# Interfaces.net
KiCad netlist of a schematic drawn in Altium Designer
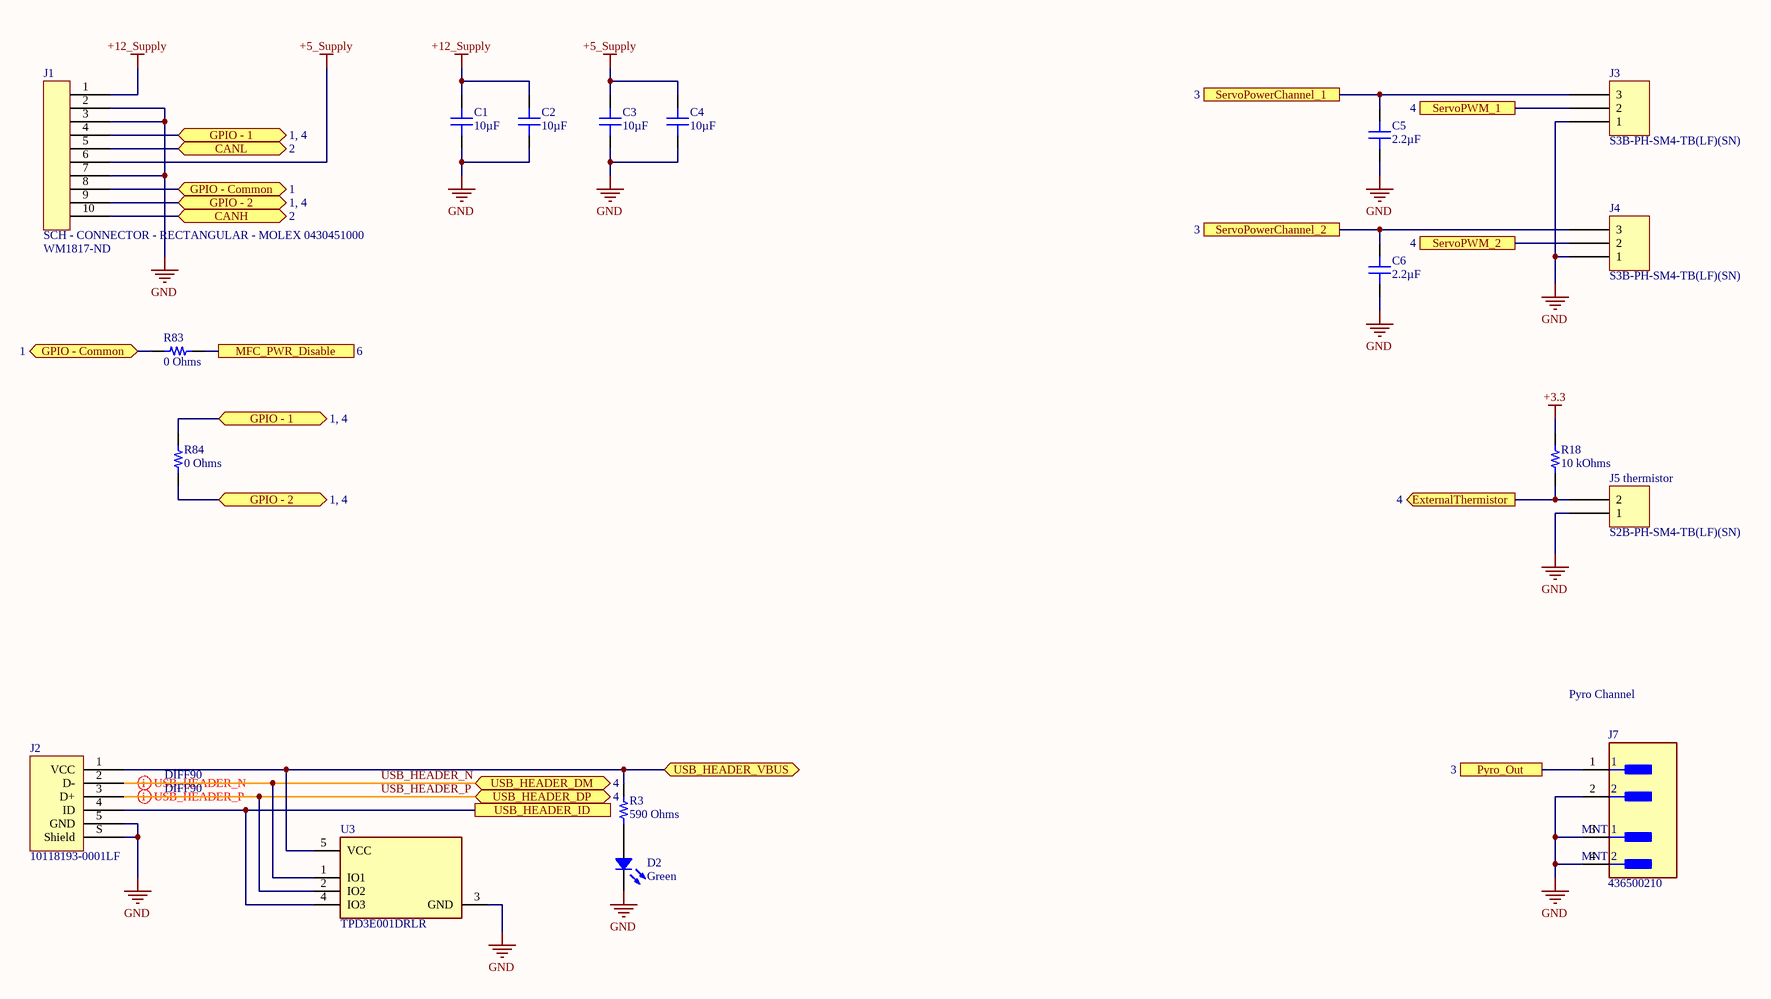
[diagram p0: Interfaces.SchDoc]

(export (version "E")
  (design (tool "Eeschema 10.0.6"))
  (components
    (comp (ref "C1")
      (value "10µF")
      (footprint "CAP 0805_2012")
      (description "CAP CER 10UF 16V X5R 0805")
      (fields (field (name "PART NUMBER") "CC0805KKX5R7BB106") (field (name "MANUFACTURER") "Yageo"))
      (libsource (lib "Celestial Altium Library - altium_library") (part "Capacitor"))
    )
    (comp (ref "C2")
      (value "10µF")
      (footprint "CAP 0805_2012")
      (description "CAP CER 10UF 16V X5R 0805")
      (fields (field (name "PART NUMBER") "CC0805KKX5R7BB106") (field (name "MANUFACTURER") "Yageo"))
      (libsource (lib "Celestial Altium Library - altium_library") (part "Capacitor"))
    )
    (comp (ref "C3")
      (value "10µF")
      (footprint "CAP 0805_2012")
      (description "CAP CER 10UF 16V X5R 0805")
      (fields (field (name "PART NUMBER") "CC0805KKX5R7BB106") (field (name "MANUFACTURER") "Yageo"))
      (libsource (lib "Celestial Altium Library - altium_library") (part "Capacitor"))
    )
    (comp (ref "C4")
      (value "10µF")
      (footprint "CAP 0805_2012")
      (description "CAP CER 10UF 16V X5R 0805")
      (fields (field (name "PART NUMBER") "CC0805KKX5R7BB106") (field (name "MANUFACTURER") "Yageo"))
      (libsource (lib "Celestial Altium Library - altium_library") (part "Capacitor"))
    )
    (comp (ref "C5")
      (value "2.2µF")
      (footprint "CAP 0603_1608")
      (description "CAP CER 2.2UF 16V X5R 0603")
      (fields (field (name "PART NUMBER") "EMK107BJ225KA-T") (field (name "MANUFACTURER") "Taiyo Yuden"))
      (libsource (lib "Celestial Altium Library - altium_library") (part "Capacitor"))
    )
    (comp (ref "C6")
      (value "2.2µF")
      (footprint "CAP 0603_1608")
      (description "CAP CER 2.2UF 16V X5R 0603")
      (fields (field (name "PART NUMBER") "EMK107BJ225KA-T") (field (name "MANUFACTURER") "Taiyo Yuden"))
      (libsource (lib "Celestial Altium Library - altium_library") (part "Capacitor"))
    )
    (comp (ref "D2")
      (value "Green")
      (footprint "LED 0603_1608 GREEN")
      (description "LED GREEN CLEAR CHIP SMD")
      (fields (field (name "PART NUMBER") "LTST-C193KGKT-5A") (field (name "MANUFACTURER") "Lite-On Inc."))
      (libsource (lib "Celestial Altium Library - altium_library") (part "LED"))
    )
    (comp (ref "J1")
      (value "SCH - CONNECTOR - RECTANGULAR - MOLEX 0430451000")
      (footprint "PCB - CONNECTOR - RECTANGULAR - MOLEX 0430451000")
      (fields (field (name "SUPPLIER PART NUMBER 1") "WM1817-ND"))
      (libsource (lib "HAB_Connectors") (part "SCH - CONNECTOR - RECTANGULAR - MOLEX 0430451000"))
    )
    (comp (ref "J2")
      (value "10118193-0001LF")
      (footprint "FCI USB 10118193-0001LF")
      (description "CONN RCPT USB2.0 MICRO B SMD R/A")
      (fields (field (name "MANUFACTURER") "Amphenol ICC (FCI)"))
      (libsource (lib "Celestial Altium Library - altium_library") (part "USB 2.0 Type B Micro"))
    )
    (comp (ref "J3")
      (value "S3B-PH-SM4-TB(LF)(SN)")
      (footprint "JST S3B-PH-SM4-TB")
      (description "CONN HEADER SMD R/A 3POS 2MM")
      (fields (field (name "MANUFACTURER") "JST Sales America Inc."))
      (libsource (lib "Celestial Altium Library - altium_library") (part "3 Pin"))
    )
    (comp (ref "J4")
      (value "S3B-PH-SM4-TB(LF)(SN)")
      (footprint "JST S3B-PH-SM4-TB")
      (description "CONN HEADER SMD R/A 3POS 2MM")
      (fields (field (name "MANUFACTURER") "JST Sales America Inc."))
      (libsource (lib "Celestial Altium Library - altium_library") (part "3 Pin"))
    )
    (comp (ref "J5")
      (value "S2B-PH-SM4-TB(LF)(SN)")
      (footprint "JST S2B-PH-SM4-TB")
      (description "CONN HEADER SMD R/A 2POS 2MM")
      (fields (field (name "MANUFACTURER") "JST Sales America Inc."))
      (libsource (lib "Celestial Altium Library - altium_library") (part "2 Pin"))
    )
    (comp (ref "J7")
      (value "436500210")
      (footprint "FP-436500210-MFG")
      (description "CONN HEADER SMD R/A 2POS 3MM")
      (fields
        (field (name "MANUFACTURER") "Molex")
        (field (name "OCTOPART") "https://octopart.com/43650-0210-molex-298097")
      )
      (libsource (lib "Altium Content Vault") (part "029478cb6d4f2fad0cd2a245525ee6d"))
    )
    (comp (ref "R3")
      (value "590 Ohms")
      (footprint "RES 0603_1608")
      (description "RES 590 OHM 1% 1/10W 0603")
      (fields
        (field (name "PART NUMBER") "RMCF0603FT590R")
        (field (name "MANUFACTURER") "Stackpole Electronics Inc")
      )
      (libsource (lib "Celestial Altium Library - altium_library") (part "Resistor"))
    )
    (comp (ref "R18")
      (value "10 kOhms")
      (footprint "RES 0603_1608")
      (description "RES 10K OHM 1% 1/10W 0603")
      (fields
        (field (name "PART NUMBER") "RMCF0603FT10K0")
        (field (name "MANUFACTURER") "Stackpole Electronics Inc")
      )
      (libsource (lib "Celestial Altium Library - altium_library") (part "Resistor"))
    )
    (comp (ref "R83")
      (value "0 Ohms")
      (footprint "RES 0603_1608")
      (description "RES 0 OHM JUMPER 1/10W 0603")
      (fields
        (field (name "PART NUMBER") "RMCF0603ZT0R00")
        (field (name "MANUFACTURER") "Stackpole Electronics Inc")
      )
      (libsource (lib "Celestial Altium Library - altium_library") (part "Resistor"))
    )
    (comp (ref "R84")
      (value "0 Ohms")
      (footprint "RES 0603_1608")
      (description "RES 0 OHM JUMPER 1/10W 0603")
      (fields
        (field (name "PART NUMBER") "RMCF0603ZT0R00")
        (field (name "MANUFACTURER") "Stackpole Electronics Inc")
      )
      (libsource (lib "Celestial Altium Library - altium_library") (part "Resistor"))
    )
    (comp (ref "U3")
      (value "TPD3E001DRLR")
      (footprint "FP-DRL0005A-MFG")
      (description "TVS DIODE 5.5V SOT5")
      (libsource (lib "Altium Content Vault") (part "867ba43d99b3a33c275ad84274a843c"))
    )
  )
  (nets
    (net (code "1") (name "+3.3") (class "Default")
      (node (ref "R18") (pin "2") (pinfunction "2_2") (pintype "passive"))
    )
    (net (code "2") (name "+5_Supply") (class "Default")
      (node (ref "C3") (pin "2") (pinfunction "2_2") (pintype "passive"))
      (node (ref "C4") (pin "2") (pinfunction "2_2") (pintype "passive"))
      (node (ref "J1") (pin "6") (pintype "passive"))
    )
    (net (code "3") (name "+12_Supply") (class "Default")
      (node (ref "C1") (pin "2") (pinfunction "2_2") (pintype "passive"))
      (node (ref "C2") (pin "2") (pinfunction "2_2") (pintype "passive"))
      (node (ref "J1") (pin "1") (pintype "passive"))
    )
    (net (code "4") (name "/CANH") (class "Default") (node (ref "J1") (pin "10") (pintype "passive")))
    (net (code "5") (name "/CANL") (class "Default") (node (ref "J1") (pin "5") (pintype "passive")))
    (net (code "6") (name "/ExternalThermistor") (class "Default")
      (node (ref "J5") (pin "2") (pinfunction "2_2") (pintype "passive"))
      (node (ref "R18") (pin "1") (pinfunction "1_1") (pintype "passive"))
    )
    (net (code "7") (name "/GPIO - 1") (class "Default")
      (node (ref "J1") (pin "4") (pintype "passive"))
      (node (ref "R84") (pin "2") (pinfunction "2_2") (pintype "passive"))
    )
    (net (code "8") (name "/GPIO - 2") (class "Default")
      (node (ref "J1") (pin "9") (pintype "passive"))
      (node (ref "R84") (pin "1") (pinfunction "1_1") (pintype "passive"))
    )
    (net (code "9") (name "/GPIO - Common") (class "Default")
      (node (ref "J1") (pin "8") (pintype "passive"))
      (node (ref "R83") (pin "1") (pinfunction "1_1") (pintype "passive"))
    )
    (net (code "10") (name "/MFC_PWR_Disable") (class "Default")
      (node (ref "R83") (pin "2") (pinfunction "2_2") (pintype "passive"))
    )
    (net (code "11") (name "/Pyro_Out") (class "Default")
      (node (ref "J7") (pin "1") (pinfunction "1_1") (pintype "passive"))
    )
    (net (code "12") (name "/ServoPWM_1") (class "Default")
      (node (ref "J3") (pin "2") (pinfunction "2_2") (pintype "passive"))
    )
    (net (code "13") (name "/ServoPWM_2") (class "Default")
      (node (ref "J4") (pin "2") (pinfunction "2_2") (pintype "passive"))
    )
    (net (code "14") (name "/ServoPowerChannel_1") (class "Default")
      (node (ref "C5") (pin "2") (pinfunction "2_2") (pintype "passive"))
      (node (ref "J3") (pin "3") (pinfunction "3_3") (pintype "passive"))
    )
    (net (code "15") (name "/ServoPowerChannel_2") (class "Default")
      (node (ref "C6") (pin "2") (pinfunction "2_2") (pintype "passive"))
      (node (ref "J4") (pin "3") (pinfunction "3_3") (pintype "passive"))
    )
    (net (code "16") (name "/USB_HEADER_ID") (class "Default")
      (node (ref "J2") (pin "4") (pinfunction "ID_4") (pintype "passive"))
      (node (ref "U3") (pin "4") (pinfunction "IO3_4") (pintype "passive"))
    )
    (net (code "17") (name "/USB_HEADER_N") (class "Default")
      (node (ref "J2") (pin "2") (pinfunction "D-_2") (pintype "passive"))
      (node (ref "U3") (pin "1") (pinfunction "IO1_1") (pintype "passive"))
    )
    (net (code "18") (name "/USB_HEADER_P") (class "Default")
      (node (ref "J2") (pin "3") (pinfunction "D+_3") (pintype "passive"))
      (node (ref "U3") (pin "2") (pinfunction "IO2_2") (pintype "passive"))
    )
    (net (code "19") (name "/USB_HEADER_VBUS") (class "Default")
      (node (ref "J2") (pin "1") (pinfunction "VCC_1") (pintype "passive"))
      (node (ref "R3") (pin "2") (pinfunction "2_2") (pintype "passive"))
      (node (ref "U3") (pin "5") (pinfunction "VCC_5") (pintype "power_in"))
    )
    (net (code "20") (name "GND") (class "Default")
      (node (ref "C1") (pin "1") (pinfunction "1_1") (pintype "passive"))
      (node (ref "C2") (pin "1") (pinfunction "1_1") (pintype "passive"))
      (node (ref "C3") (pin "1") (pinfunction "1_1") (pintype "passive"))
      (node (ref "C4") (pin "1") (pinfunction "1_1") (pintype "passive"))
      (node (ref "C5") (pin "1") (pinfunction "1_1") (pintype "passive"))
      (node (ref "C6") (pin "1") (pinfunction "1_1") (pintype "passive"))
      (node (ref "D2") (pin "2") (pinfunction "2_2") (pintype "passive"))
      (node (ref "J1") (pin "2") (pintype "passive"))
      (node (ref "J1") (pin "3") (pintype "passive"))
      (node (ref "J1") (pin "7") (pintype "passive"))
      (node (ref "J2") (pin "5") (pinfunction "GND_5") (pintype "passive"))
      (node (ref "J2") (pin "S") (pinfunction "Shield_S") (pintype "passive"))
      (node (ref "J3") (pin "1") (pinfunction "1_1") (pintype "passive"))
      (node (ref "J4") (pin "1") (pinfunction "1_1") (pintype "passive"))
      (node (ref "J5") (pin "1") (pinfunction "1_1") (pintype "passive"))
      (node (ref "J7") (pin "2") (pinfunction "2_2") (pintype "passive"))
      (node (ref "J7") (pin "3") (pinfunction "MNT_1_3") (pintype "passive"))
      (node (ref "J7") (pin "4") (pinfunction "MNT_2_4") (pintype "passive"))
      (node (ref "U3") (pin "3") (pinfunction "GND_3") (pintype "power_in"))
    )
    (net (code "21") (name "Net-(D2-Pad1)") (class "Default")
      (node (ref "D2") (pin "1") (pinfunction "1_1") (pintype "passive"))
      (node (ref "R3") (pin "1") (pinfunction "1_1") (pintype "passive"))
    )
  )
)
